# PWR_CHGR.net
KiCad netlist of a schematic drawn in Altium Designer
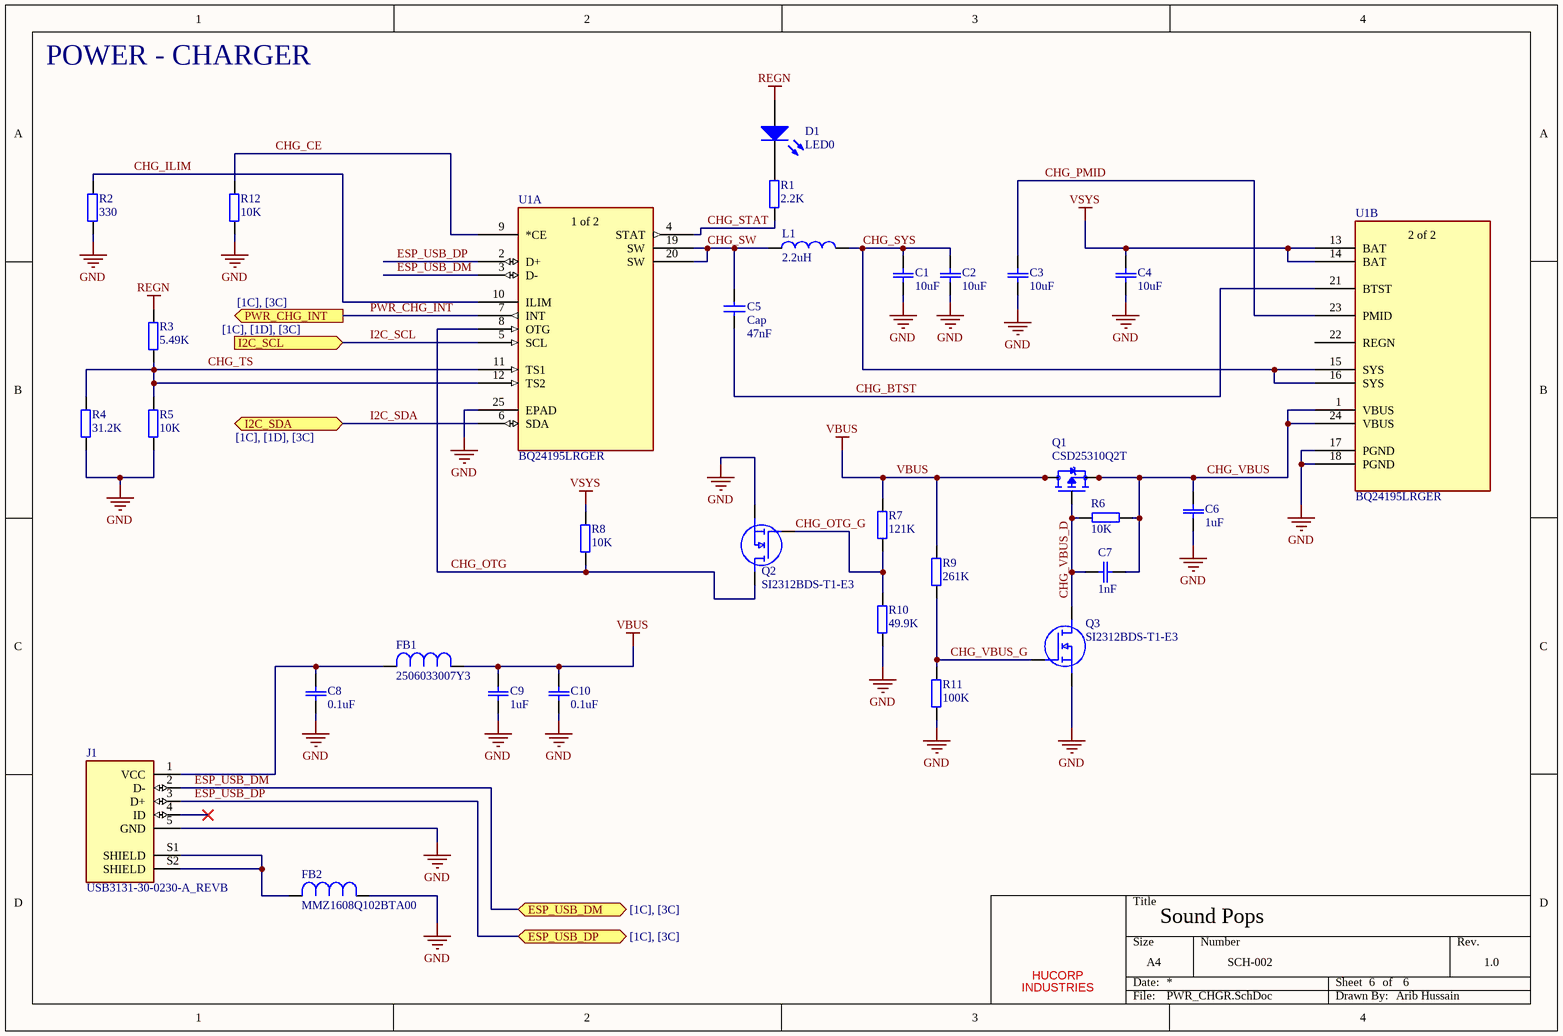
[diagram p0: PWR_CHGR.SchDoc]

(export (version "E")
  (design (tool "Eeschema 10.0.6"))
  (components
    (comp (ref "C1")
      (value "10uF")
      (footprint "CAP_CL10_SAM")
      (description "10 µF ±20% 6.3V Ceramic Capacitor X5R 0603 (1608 Metric)")
      (fields
        (field (name "MANUFACTURER_PART_NUMBER") "CL10A106MQ8NNNC")
        (field (name "Comment") "10 uF")
        (field (name "COPYRIGHT") "Copyright (C) 2022 Ultra Librarian. All rights reserved.")
      )
      (libsource (lib "Capacitors") (part "CL10A106MQ8NNNC"))
    )
    (comp (ref "C2")
      (value "10uF")
      (footprint "CAP_CL10_SAM")
      (description "10 µF ±20% 6.3V Ceramic Capacitor X5R 0603 (1608 Metric)")
      (fields
        (field (name "MANUFACTURER_PART_NUMBER") "CL10A106MQ8NNNC")
        (field (name "Comment") "10 uF")
        (field (name "COPYRIGHT") "Copyright (C) 2022 Ultra Librarian. All rights reserved.")
      )
      (libsource (lib "Capacitors") (part "CL10A106MQ8NNNC"))
    )
    (comp (ref "C3")
      (value "10uF")
      (footprint "CAP_CL10_SAM")
      (description "10 µF ±20% 6.3V Ceramic Capacitor X5R 0603 (1608 Metric)")
      (fields
        (field (name "MANUFACTURER_PART_NUMBER") "CL10A106MQ8NNNC")
        (field (name "Comment") "10 uF")
        (field (name "COPYRIGHT") "Copyright (C) 2022 Ultra Librarian. All rights reserved.")
      )
      (libsource (lib "Capacitors") (part "CL10A106MQ8NNNC"))
    )
    (comp (ref "C4")
      (value "10uF")
      (footprint "CAP_CL10_SAM")
      (description "10 µF ±20% 6.3V Ceramic Capacitor X5R 0603 (1608 Metric)")
      (fields
        (field (name "MANUFACTURER_PART_NUMBER") "CL10A106MQ8NNNC")
        (field (name "Comment") "10 uF")
        (field (name "COPYRIGHT") "Copyright (C) 2022 Ultra Librarian. All rights reserved.")
      )
      (libsource (lib "Capacitors") (part "CL10A106MQ8NNNC"))
    )
    (comp (ref "C5")
      (value "Cap")
      (footprint "RAD-0.3")
      (description "Capacitor")
      (fields (field (name "ALTIUM_VALUE") "47nF") (field (name "PUBLISHER") "Altium Limited"))
      (libsource (lib "Miscellaneous Devices") (part "Cap"))
    )
    (comp (ref "C6")
      (value "1uF")
      (footprint "CAP_CL10_SAM")
      (description "CAP CER 1UF 25V X5R 0603")
      (fields
        (field (name "MANUFACTURER_PART_NUMBER") "CL10B104KA8NNNC")
        (field (name "COPYRIGHT") "Copyright (C) 2022 Ultra Librarian. All rights reserved.")
      )
      (libsource (lib "Capacitors") (part "CL10A105KA8NNNC"))
    )
    (comp (ref "C7")
      (value "1nF")
      (footprint "CAP_CL10_SAM")
      (description "CAP CER 1nF 50V X7R 0603")
      (fields
        (field (name "MANUFACTURER_PART_NUMBER") "CL10B102KB8NFNC")
        (field (name "Comment") "1 nF")
        (field (name "COPYRIGHT") "Copyright (C) 2023 Ultra Librarian. All rights reserved.")
      )
      (libsource (lib "Capacitors") (part "CL10B102KB8NFNC"))
    )
    (comp (ref "C8")
      (value "0.1uF")
      (footprint "CAP_CL10_SAM")
      (description "CAP CER 0.1UF 25V X7R 0603")
      (fields
        (field (name "MANUFACTURER_PART_NUMBER") "CL10B104KA8NNNC")
        (field (name "Comment") "100 nF")
        (field (name "COPYRIGHT") "Copyright (C) 2022 Ultra Librarian. All rights reserved.")
      )
      (libsource (lib "Capacitors") (part "CL10B104KA8NNNC"))
    )
    (comp (ref "C9")
      (value "1uF")
      (footprint "CAP_CL10_SAM")
      (description "CAP CER 1UF 25V X5R 0603")
      (fields
        (field (name "MANUFACTURER_PART_NUMBER") "CL10B104KA8NNNC")
        (field (name "COPYRIGHT") "Copyright (C) 2022 Ultra Librarian. All rights reserved.")
      )
      (libsource (lib "Capacitors") (part "CL10A105KA8NNNC"))
    )
    (comp (ref "C10")
      (value "0.1uF")
      (footprint "CAP_CL10_SAM")
      (description "CAP CER 0.1UF 25V X7R 0603")
      (fields
        (field (name "MANUFACTURER_PART_NUMBER") "CL10B104KA8NNNC")
        (field (name "Comment") "100 nF")
        (field (name "COPYRIGHT") "Copyright (C) 2022 Ultra Librarian. All rights reserved.")
      )
      (libsource (lib "Capacitors") (part "CL10B104KA8NNNC"))
    )
    (comp (ref "D1")
      (value "LED0")
      (footprint "LED-0")
      (description "Typical INFRARED GaAs LED")
      (fields (field (name "PUBLISHER") "Altium Limited"))
      (libsource (lib "Miscellaneous Devices") (part "LED0"))
    )
    (comp (ref "FB1")
      (value "2506033007Y3")
      (footprint "IND_25_0603_FRT")
      (description "FERRITE BEAD 30 OHM 0603 1LN")
      (fields (field (name "COPYRIGHT") "Copyright (C) 2023 Ultra Librarian. All rights reserved."))
      (libsource (lib "PASSIVES") (part "2506033007Y3"))
    )
    (comp (ref "FB2")
      (value "MMZ1608Q102BTA00")
      (footprint "IND_1608_TDK")
      (description "FERRITE BEAD 1K OHM 0603 1LN")
      (fields (field (name "COPYRIGHT") "Copyright (C) 2023 Ultra Librarian. All rights reserved."))
      (libsource (lib "PASSIVES") (part "MMZ1608Q102BTA00"))
    )
    (comp (ref "J1")
      (value "USB3131-30-0230-A_REVB")
      (footprint "GCT_USB3131-30-0230-A_REVB:GCT_USB3131-30-0230-A_REVB")
      (description "USB - micro B USB 2.0 Receptacle Connector 5 Position Through Hole")
      (libsource (lib "MISC") (part "USB3131-30-0230-A_REVB"))
    )
    (comp (ref "L1")
      (value "2.2uH")
      (footprint "PASSIVES:INDC2520X100N")
      (description "Inductor with Inductance: 2.2uH Tol. +/-20%, Package: 1008 (2520)")
      (fields (field (name "MP") "DFE252010P-2R2M=P2") (field (name "MF") "Murata Electronics"))
      (libsource (lib "PASSIVES") (part "DFE252010P-2R2M=P2"))
    )
    (comp (ref "Q1")
      (value "CSD25310Q2T")
      (footprint "TRANS_CSD25310Q2T:TRANS_CSD25310Q2T")
      (description "-20V, P ch NexFET MOSFET, single SON 2x2, 23.9mOhm 6-WSON -55 to 150")
      (fields (field (name "DIGI-KEY_PART_NUMBER") "296-50290-2-ND") (field (name "MF") "Texas Instruments"))
      (libsource (lib "MISC") (part "CSD25310Q2T"))
    )
    (comp (ref "Q2")
      (value "SI2312BDS-T1-E3")
      (footprint "SOT95P237X112-3N")
      (description "N-Channel 20 V (D-S) MOSFET")
      (fields (field (name "MOUSER PART NUMBER") "781-SI2312BDS-E3"))
      (libsource (lib "MISC") (part "SI2312BDS-T1-E3"))
    )
    (comp (ref "Q3")
      (value "SI2312BDS-T1-E3")
      (footprint "SOT95P237X112-3N")
      (description "N-Channel 20 V (D-S) MOSFET")
      (fields (field (name "MOUSER PART NUMBER") "781-SI2312BDS-E3"))
      (libsource (lib "MISC") (part "SI2312BDS-T1-E3"))
    )
    (comp (ref "R1")
      (value "2.2K")
      (footprint "RC0603N_YAG")
      (description "RES 2.2K OHM 1% 1/10W 0603")
      (fields
        (field (name "MANUFACTURER_PART_NUMBER") "RC0603FR-072K2L")
        (field (name "COPYRIGHT") "Copyright (C) 2023 Ultra Librarian. All rights reserved.")
      )
      (libsource (lib "Resistors") (part "RC0603FR-072K2L"))
    )
    (comp (ref "R2")
      (value "330")
      (footprint "RES_RC0603_YAG")
      (description "RES 330 OHM 1% 1/10W 0603")
      (fields
        (field (name "MANUFACTURER_PART_NUMBER") "RC0603FR-13330RL")
        (field (name "COPYRIGHT") "Copyright (C) 2023 Ultra Librarian. All rights reserved.")
      )
      (libsource (lib "Resistors") (part "RC0603FR-13330RL"))
    )
    (comp (ref "R3")
      (value "5.49K")
      (footprint "RC0603N_YAG")
      (description "RES 5.49K OHM 1% 1/10W 0603")
      (fields
        (field (name "MANUFACTURER_PART_NUMBER") "RC0603FR-075K49L")
        (field (name "COPYRIGHT") "Copyright (C) 2023 Ultra Librarian. All rights reserved.")
      )
      (libsource (lib "Resistors") (part "RC0603FR-075K49L"))
    )
    (comp (ref "R4")
      (value "31.2K")
      (footprint "RESC1608X55N")
      (description "RES 31.2K OHM 0.5% 1/10W 0603")
      (fields (field (name "MP") "RT0603DRE0731K2L"))
      (libsource (lib "Resistors") (part "RT0603DRE0731K2L"))
    )
    (comp (ref "R5")
      (value "10K")
      (footprint "RES_RC0603_YAG")
      (description "RES 10K OHM 5% 1/10W 0603")
      (fields
        (field (name "MANUFACTURER_PART_NUMBER") "RC0603JR-1310KL")
        (field (name "COPYRIGHT") "Copyright (C) 2022 Ultra Librarian. All rights reserved.")
      )
      (libsource (lib "Resistors") (part "RC0603JR-1310KL"))
    )
    (comp (ref "R6")
      (value "10K")
      (footprint "RES_RC0603_YAG")
      (description "RES 10K OHM 5% 1/10W 0603")
      (fields
        (field (name "MANUFACTURER_PART_NUMBER") "RC0603JR-1310KL")
        (field (name "COPYRIGHT") "Copyright (C) 2022 Ultra Librarian. All rights reserved.")
      )
      (libsource (lib "Resistors") (part "RC0603JR-1310KL"))
    )
    (comp (ref "R7")
      (value "121K")
      (footprint "RC0603N_YAG")
      (description "RES 121K OHM 1% 1/10W 0603")
      (fields
        (field (name "MANUFACTURER_PART_NUMBER") "RC0603FR-07121KL")
        (field (name "COPYRIGHT") "Copyright (C) 2023 Ultra Librarian. All rights reserved.")
      )
      (libsource (lib "Resistors") (part "RC0603FR-07121KL"))
    )
    (comp (ref "R8")
      (value "10K")
      (footprint "RES_RC0603_YAG")
      (description "RES 10K OHM 5% 1/10W 0603")
      (fields
        (field (name "MANUFACTURER_PART_NUMBER") "RC0603JR-1310KL")
        (field (name "COPYRIGHT") "Copyright (C) 2022 Ultra Librarian. All rights reserved.")
      )
      (libsource (lib "Resistors") (part "RC0603JR-1310KL"))
    )
    (comp (ref "R9")
      (value "261K")
      (footprint "RC0603N_YAG")
      (description "RES 261K OHM 1% 1/10W 0603")
      (fields
        (field (name "MANUFACTURER_PART_NUMBER") "RC0603FR-07261KL")
        (field (name "COPYRIGHT") "Copyright (C) 2023 Ultra Librarian. All rights reserved.")
      )
      (libsource (lib "Resistors") (part "RC0603FR-07261KL"))
    )
    (comp (ref "R10")
      (value "49.9K")
      (footprint "RES_RC0603_YAG")
      (description "RES 49.9K OHM 1% 1/10W 0603")
      (fields
        (field (name "MANUFACTURER_PART_NUMBER") "RC0603FR-1049K9L")
        (field (name "COPYRIGHT") "Copyright (C) 2023 Ultra Librarian. All rights reserved.")
      )
      (libsource (lib "Resistors") (part "RC0603FR-1049K9L"))
    )
    (comp (ref "R11")
      (value "100K")
      (footprint "RC0603N_YAG")
      (description "RES 100K OHM 1% 1/10W 0603")
      (fields
        (field (name "MANUFACTURER_PART_NUMBER") "RC0603FR-07100KL")
        (field (name "COPYRIGHT") "Copyright (C) 2022 Ultra Librarian. All rights reserved.")
      )
      (libsource (lib "Resistors") (part "RC0603FR-07100KL"))
    )
    (comp (ref "R12")
      (value "10K")
      (footprint "RES_RC0603_YAG")
      (description "RES 10K OHM 5% 1/10W 0603")
      (fields
        (field (name "MANUFACTURER_PART_NUMBER") "RC0603JR-1310KL")
        (field (name "COPYRIGHT") "Copyright (C) 2022 Ultra Librarian. All rights reserved.")
      )
      (libsource (lib "Resistors") (part "RC0603JR-1310KL"))
    )
    (comp (ref "U1")
      (value "BQ24195LRGER")
      (footprint "RGE24_2P7X2P7_TEX")
      (description "IC BATT CHG LI-ION 1CELL 24VQFN")
      (fields (field (name "COPYRIGHT") "Copyright (C) 2023 Ultra Librarian. All rights reserved."))
      (libsource (lib "MISC") (part "BQ24195LRGER"))
    )
  )
  (nets
    (net (code "1") (name "/CHG_BTST") (class "Default")
      (node (ref "C5") (pin "1") (pinfunction "1_1") (pintype "passive"))
      (node (ref "U1") (pin "21") (pinfunction "BTST_21") (pintype "power_in"))
    )
    (net (code "2") (name "/CHG_CE") (class "Default")
      (node (ref "R12") (pin "2") (pinfunction "2_2") (pintype "passive"))
      (node (ref "U1") (pin "9") (pinfunction "*CE_9") (pintype "passive"))
    )
    (net (code "3") (name "/CHG_ILIM") (class "Default")
      (node (ref "R2") (pin "2") (pinfunction "2_2") (pintype "passive"))
      (node (ref "U1") (pin "10") (pinfunction "ILIM_10") (pintype "passive"))
    )
    (net (code "4") (name "/CHG_OTG") (class "Default")
      (node (ref "Q2") (pin "3") (pinfunction "D_3") (pintype "passive"))
      (node (ref "R8") (pin "1") (pinfunction "1_1") (pintype "passive"))
      (node (ref "U1") (pin "8") (pinfunction "OTG_8") (pintype "input"))
    )
    (net (code "5") (name "/CHG_OTG_G") (class "Default")
      (node (ref "Q2") (pin "1") (pinfunction "G_1") (pintype "passive"))
      (node (ref "R10") (pin "2") (pinfunction "2_2") (pintype "passive"))
      (node (ref "R7") (pin "1") (pinfunction "1_1") (pintype "passive"))
    )
    (net (code "6") (name "/CHG_PMID") (class "Default")
      (node (ref "C3") (pin "2") (pinfunction "2_2") (pintype "passive"))
      (node (ref "U1") (pin "23") (pinfunction "PMID_23") (pintype "power_in"))
    )
    (net (code "7") (name "/CHG_STAT") (class "Default")
      (node (ref "R1") (pin "1") (pinfunction "1_1") (pintype "passive"))
      (node (ref "U1") (pin "4") (pinfunction "STAT_4") (pintype "output"))
    )
    (net (code "8") (name "/CHG_SW") (class "Default")
      (node (ref "C5") (pin "2") (pinfunction "2_2") (pintype "passive"))
      (node (ref "L1") (pin "1") (pinfunction "1_1") (pintype "passive"))
      (node (ref "U1") (pin "19") (pinfunction "SW_19") (pintype "passive"))
      (node (ref "U1") (pin "20") (pinfunction "SW_20") (pintype "passive"))
    )
    (net (code "9") (name "/CHG_SYS") (class "Default")
      (node (ref "C1") (pin "2") (pinfunction "2_2") (pintype "passive"))
      (node (ref "C2") (pin "2") (pinfunction "2_2") (pintype "passive"))
      (node (ref "L1") (pin "2") (pinfunction "2_2") (pintype "passive"))
      (node (ref "U1") (pin "15") (pinfunction "SYS_15") (pintype "power_in"))
      (node (ref "U1") (pin "16") (pinfunction "SYS_16") (pintype "power_in"))
    )
    (net (code "10") (name "/CHG_TS") (class "Default")
      (node (ref "R3") (pin "1") (pinfunction "1_1") (pintype "passive"))
      (node (ref "R4") (pin "2") (pinfunction "2_2") (pintype "passive"))
      (node (ref "R5") (pin "2") (pinfunction "2_2") (pintype "passive"))
      (node (ref "U1") (pin "11") (pinfunction "TS1_11") (pintype "input"))
      (node (ref "U1") (pin "12") (pinfunction "TS2_12") (pintype "input"))
    )
    (net (code "11") (name "/CHG_VBUS") (class "Default")
      (node (ref "C6") (pin "2") (pinfunction "2_2") (pintype "passive"))
      (node (ref "C7") (pin "2") (pinfunction "2_2") (pintype "passive"))
      (node (ref "Q1") (pin "1") (pinfunction "S_1") (pintype "passive"))
      (node (ref "Q1") (pin "2") (pinfunction "S_2") (pintype "passive"))
      (node (ref "Q1") (pin "5") (pinfunction "S_5") (pintype "passive"))
      (node (ref "Q1") (pin "6") (pinfunction "S_6") (pintype "passive"))
      (node (ref "Q1") (pin "7") (pinfunction "S_7") (pintype "passive"))
      (node (ref "R6") (pin "2") (pinfunction "2_2") (pintype "passive"))
      (node (ref "U1") (pin "1") (pinfunction "VBUS_1") (pintype "power_in"))
      (node (ref "U1") (pin "24") (pinfunction "VBUS_24") (pintype "power_in"))
    )
    (net (code "12") (name "/CHG_VBUS_D") (class "Default")
      (node (ref "C7") (pin "1") (pinfunction "1_1") (pintype "passive"))
      (node (ref "Q1") (pin "3") (pinfunction "G_3") (pintype "passive"))
      (node (ref "Q3") (pin "3") (pinfunction "D_3") (pintype "passive"))
      (node (ref "R6") (pin "1") (pinfunction "1_1") (pintype "passive"))
    )
    (net (code "13") (name "/CHG_VBUS_G") (class "Default")
      (node (ref "Q3") (pin "1") (pinfunction "G_1") (pintype "passive"))
      (node (ref "R11") (pin "2") (pinfunction "2_2") (pintype "passive"))
      (node (ref "R9") (pin "1") (pinfunction "1_1") (pintype "passive"))
    )
    (net (code "14") (name "/ESP_USB_DM") (class "Default")
      (node (ref "J1") (pin "2") (pinfunction "D-_2") (pintype "bidirectional"))
      (node (ref "U1") (pin "3") (pinfunction "D-_3") (pintype "bidirectional"))
    )
    (net (code "15") (name "/ESP_USB_DP") (class "Default")
      (node (ref "J1") (pin "3") (pinfunction "D+_3") (pintype "bidirectional"))
      (node (ref "U1") (pin "2") (pinfunction "D+_2") (pintype "bidirectional"))
    )
    (net (code "16") (name "/I2C_SCL") (class "Default")
      (node (ref "U1") (pin "5") (pinfunction "SCL_5") (pintype "input"))
    )
    (net (code "17") (name "/I2C_SDA") (class "Default")
      (node (ref "U1") (pin "6") (pinfunction "SDA_6") (pintype "bidirectional"))
    )
    (net (code "18") (name "/PWR_CHG_INT") (class "Default")
      (node (ref "U1") (pin "7") (pinfunction "INT_7") (pintype "output"))
    )
    (net (code "19") (name "GND") (class "Default")
      (node (ref "C1") (pin "1") (pinfunction "1_1") (pintype "passive"))
      (node (ref "C10") (pin "1") (pinfunction "1_1") (pintype "passive"))
      (node (ref "C2") (pin "1") (pinfunction "1_1") (pintype "passive"))
      (node (ref "C3") (pin "1") (pinfunction "1_1") (pintype "passive"))
      (node (ref "C4") (pin "1") (pinfunction "1_1") (pintype "passive"))
      (node (ref "C6") (pin "1") (pinfunction "1_1") (pintype "passive"))
      (node (ref "C8") (pin "1") (pinfunction "1_1") (pintype "passive"))
      (node (ref "C9") (pin "1") (pinfunction "1_1") (pintype "passive"))
      (node (ref "FB2") (pin "1") (pinfunction "1_1") (pintype "passive"))
      (node (ref "J1") (pin "5") (pinfunction "GND_5") (pintype "passive"))
      (node (ref "Q2") (pin "2") (pinfunction "S_2") (pintype "passive"))
      (node (ref "Q3") (pin "2") (pinfunction "S_2") (pintype "passive"))
      (node (ref "R10") (pin "1") (pinfunction "1_1") (pintype "passive"))
      (node (ref "R11") (pin "1") (pinfunction "1_1") (pintype "passive"))
      (node (ref "R12") (pin "1") (pinfunction "1_1") (pintype "passive"))
      (node (ref "R2") (pin "1") (pinfunction "1_1") (pintype "passive"))
      (node (ref "R4") (pin "1") (pinfunction "1_1") (pintype "passive"))
      (node (ref "R5") (pin "1") (pinfunction "1_1") (pintype "passive"))
      (node (ref "U1") (pin "17") (pinfunction "PGND_17") (pintype "passive"))
      (node (ref "U1") (pin "18") (pinfunction "PGND_18") (pintype "passive"))
      (node (ref "U1") (pin "25") (pinfunction "EPAD_25") (pintype "passive"))
    )
    (net (code "20") (name "Net-(D1-K)") (class "Default")
      (node (ref "D1") (pin "2") (pinfunction "K_2") (pintype "passive"))
      (node (ref "R1") (pin "2") (pinfunction "2_2") (pintype "passive"))
    )
    (net (code "21") (name "Net-(FB2-Pad2)") (class "Default")
      (node (ref "FB2") (pin "2") (pinfunction "2_2") (pintype "passive"))
      (node (ref "J1") (pin "S1") (pinfunction "SHIELD_S1") (pintype "passive"))
      (node (ref "J1") (pin "S2") (pinfunction "SHIELD_S2") (pintype "passive"))
    )
    (net (code "22") (name "Net-(J1-VCC)") (class "Default")
      (node (ref "C8") (pin "2") (pinfunction "2_2") (pintype "passive"))
      (node (ref "FB1") (pin "2") (pinfunction "2_2") (pintype "passive"))
      (node (ref "J1") (pin "1") (pinfunction "VCC_1") (pintype "power_in"))
    )
    (net (code "23") (name "REGN") (class "Default")
      (node (ref "D1") (pin "1") (pinfunction "A_1") (pintype "passive"))
      (node (ref "R3") (pin "2") (pinfunction "2_2") (pintype "passive"))
    )
    (net (code "24") (name "VBUS") (class "Default")
      (node (ref "C10") (pin "2") (pinfunction "2_2") (pintype "passive"))
      (node (ref "C9") (pin "2") (pinfunction "2_2") (pintype "passive"))
      (node (ref "FB1") (pin "1") (pinfunction "1_1") (pintype "passive"))
      (node (ref "Q1") (pin "4") (pinfunction "D_4") (pintype "passive"))
      (node (ref "Q1") (pin "8") (pinfunction "D_8") (pintype "passive"))
      (node (ref "R7") (pin "2") (pinfunction "2_2") (pintype "passive"))
      (node (ref "R9") (pin "2") (pinfunction "2_2") (pintype "passive"))
    )
    (net (code "25") (name "VSYS") (class "Default")
      (node (ref "C4") (pin "2") (pinfunction "2_2") (pintype "passive"))
      (node (ref "R8") (pin "2") (pinfunction "2_2") (pintype "passive"))
      (node (ref "U1") (pin "13") (pinfunction "BAT_13") (pintype "power_in"))
      (node (ref "U1") (pin "14") (pinfunction "BAT_14") (pintype "power_in"))
    )
    (net (code "26") (name "unconnected-(J1-ID-Pad4)") (class "Default")
      (node (ref "J1") (pin "4") (pinfunction "ID_4") (pintype "bidirectional+no_connect"))
    )
    (net (code "27") (name "unconnected-(U1B-REGN-Pad22)") (class "Default")
      (node (ref "U1") (pin "22") (pinfunction "REGN_22") (pintype "power_in"))
    )
  )
)
